# CC40_ROM_Cart.net
KiCad netlist of a schematic drawn in EAGLE
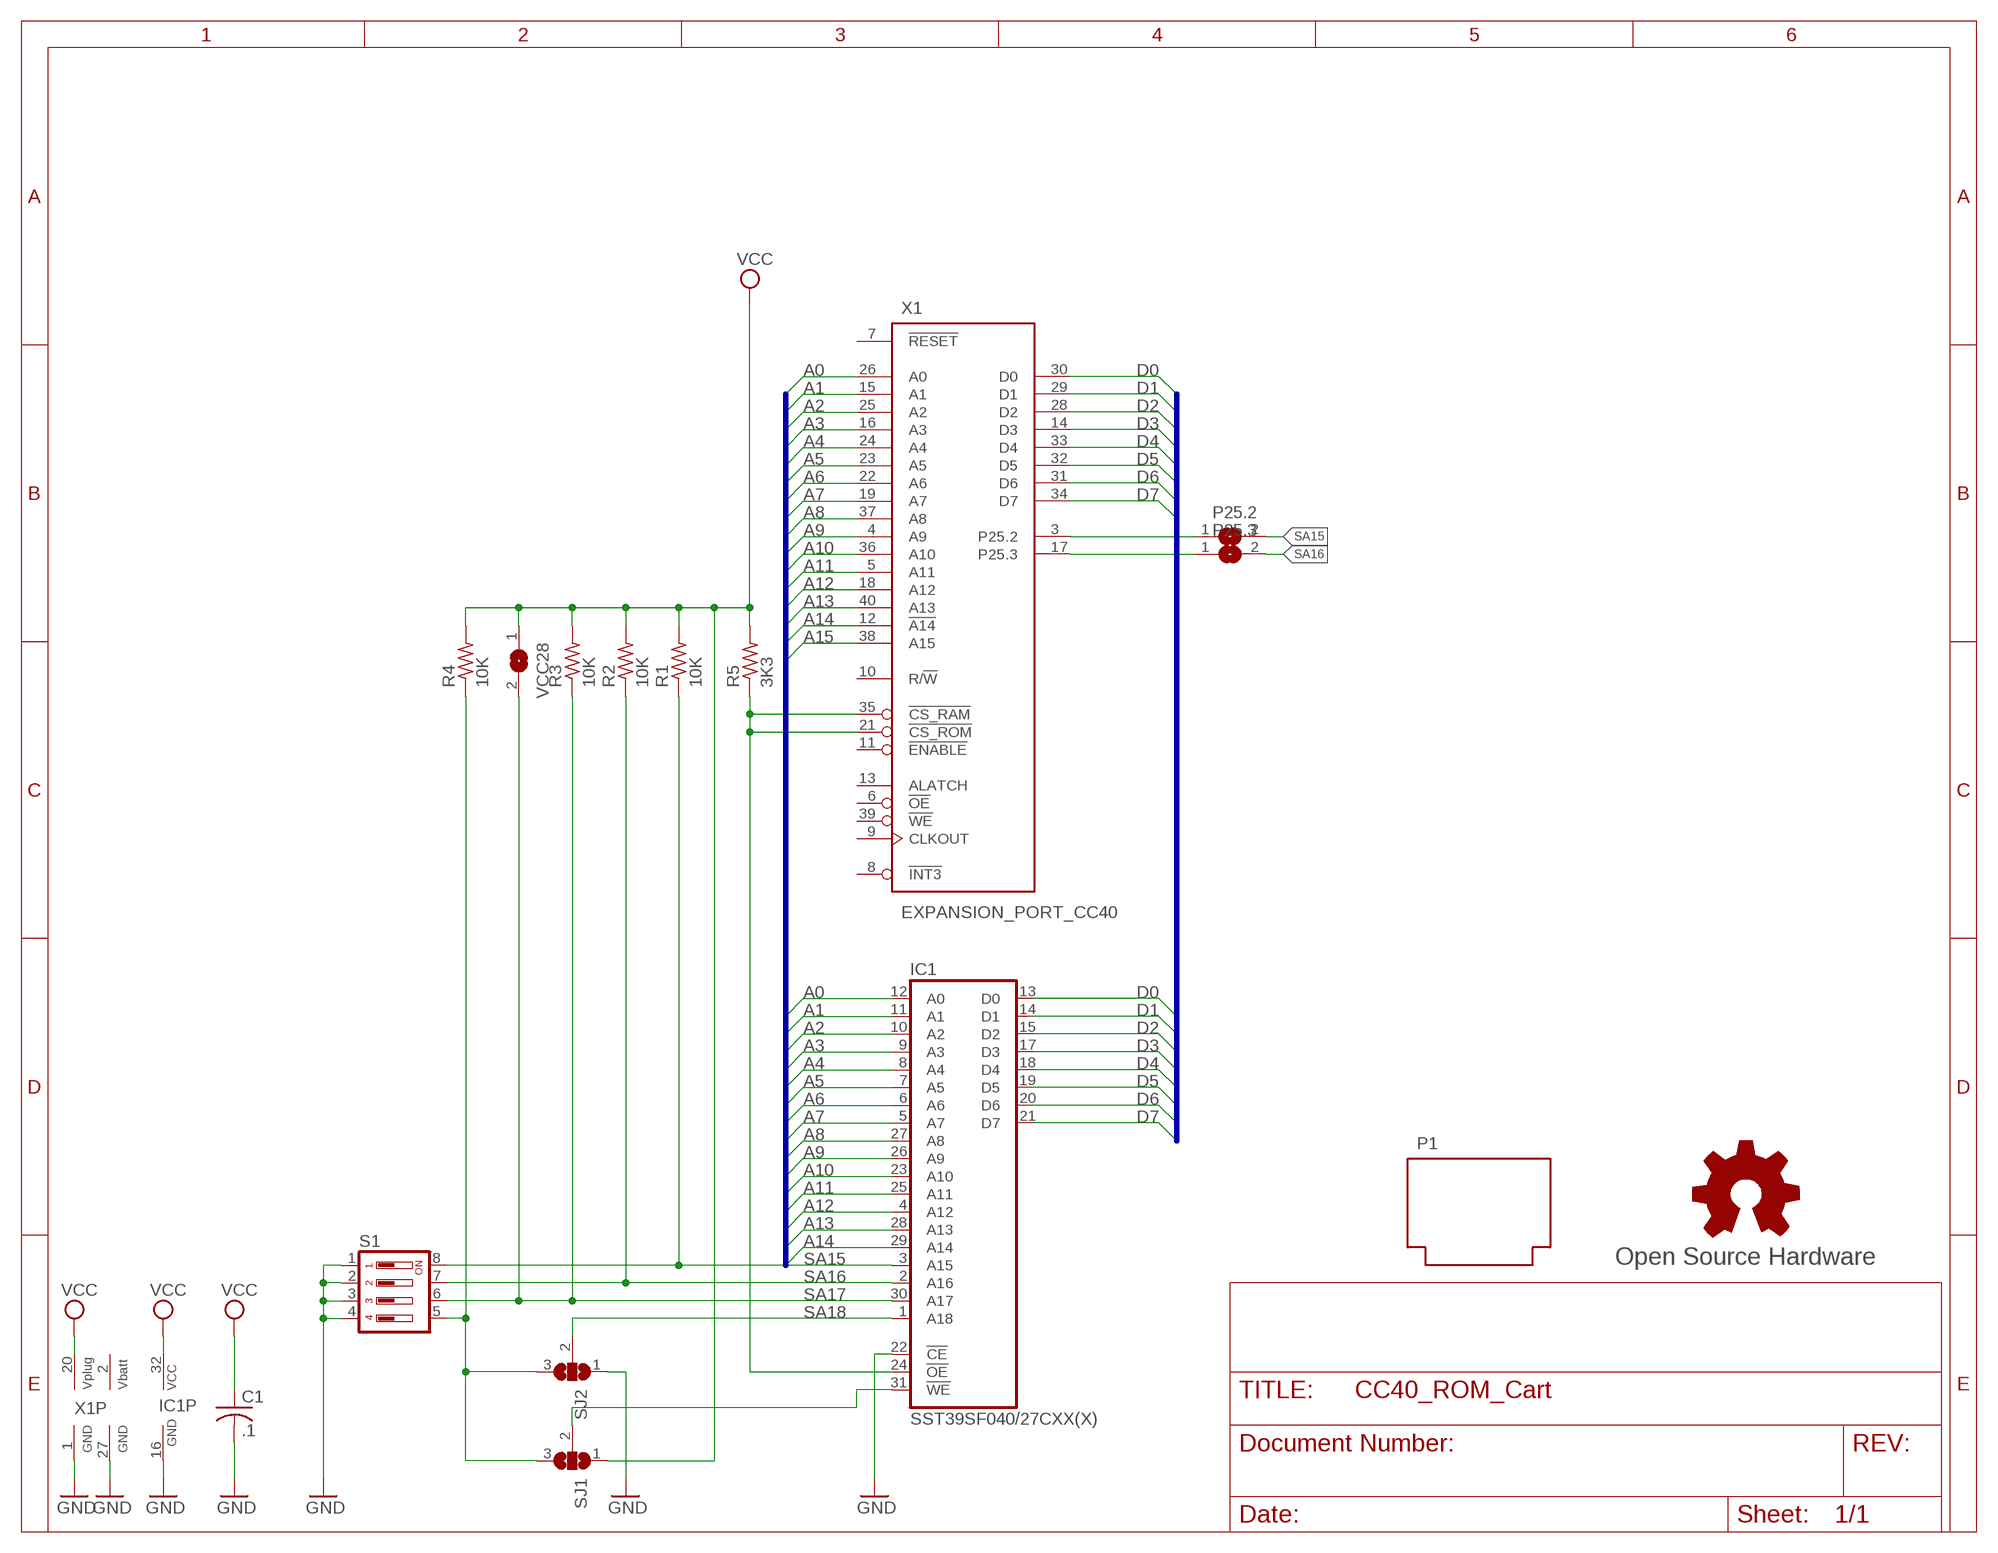
[diagram p0: schematic, sheet 1]

(export (version "E")
  (design (tool "Eeschema 10.0.6"))
  (components
    (comp (ref "C1")
      (value ".1")
      (footprint "eagle-import:C025-025X050")
      (libsource (lib "eagle-import") (part "C-US025-025X050"))
    )
    (comp (ref "GOLD_ORB_SM1")
      (value "Open Source Hardware")
      (footprint "eagle-import:OSHW_8MM")
      (libsource (lib "eagle-import") (part "OSHWLOGOLOGO8MM"))
    )
    (comp (ref "IC1")
      (value "SST39SF040/27CXX(X)")
      (footprint "eagle-import:DIL32-RP")
      (libsource (lib "eagle-import") (part "SST39SF040APHR"))
    )
    (comp (ref "P1")
      (value "CC40_CARTN")
      (footprint "eagle-import:CC40_CART_NOHOLE")
      (libsource (lib "eagle-import") (part "CC40_CARTN"))
    )
    (comp (ref "P25.2")
      (value "SJ")
      (footprint "eagle-import:SJ")
      (libsource (lib "eagle-import") (part "SJ"))
    )
    (comp (ref "P25.3")
      (value "SJ")
      (footprint "eagle-import:SJ")
      (libsource (lib "eagle-import") (part "SJ"))
    )
    (comp (ref "R1")
      (value "10K")
      (footprint "eagle-import:0204_7")
      (libsource (lib "eagle-import") (part "R-US_0204/7"))
    )
    (comp (ref "R2")
      (value "10K")
      (footprint "eagle-import:0204_7")
      (libsource (lib "eagle-import") (part "R-US_0204/7"))
    )
    (comp (ref "R3")
      (value "10K")
      (footprint "eagle-import:0204_7")
      (libsource (lib "eagle-import") (part "R-US_0204/7"))
    )
    (comp (ref "R4")
      (value "10K")
      (footprint "eagle-import:0204_7")
      (libsource (lib "eagle-import") (part "R-US_0204/7"))
    )
    (comp (ref "R5")
      (value "3K3")
      (footprint "eagle-import:0204_7")
      (libsource (lib "eagle-import") (part "R-US_0204/7"))
    )
    (comp (ref "S1")
      (value "DP04")
      (footprint "eagle-import:DP-04")
      (libsource (lib "eagle-import") (part "DP04"))
    )
    (comp (ref "SJ1")
      (value "SJ2W")
      (footprint "eagle-import:SJ_2")
      (libsource (lib "eagle-import") (part "SJ2W"))
    )
    (comp (ref "SJ2")
      (value "SJ2W")
      (footprint "eagle-import:SJ_2")
      (libsource (lib "eagle-import") (part "SJ2W"))
    )
    (comp (ref "VCC28")
      (value "SJ")
      (footprint "eagle-import:SJ")
      (libsource (lib "eagle-import") (part "SJ"))
    )
    (comp (ref "X1")
      (value "EXPANSION_PORT_CC40")
      (footprint "eagle-import:MA20-2(.050)")
      (libsource (lib "eagle-import") (part "EXPANSION_PORT_CC40"))
    )
  )
  (nets
    (net (code "1") (name "/A0") (class "Default")
      (node (ref "IC1") (pin "12") (pinfunction "A0_12") (pintype "input"))
      (node (ref "X1") (pin "26") (pinfunction "A0_26") (pintype "output"))
    )
    (net (code "2") (name "/A1") (class "Default")
      (node (ref "IC1") (pin "11") (pinfunction "A1_11") (pintype "input"))
      (node (ref "X1") (pin "15") (pinfunction "A1_15") (pintype "output"))
    )
    (net (code "3") (name "/A2") (class "Default")
      (node (ref "IC1") (pin "10") (pinfunction "A2_10") (pintype "input"))
      (node (ref "X1") (pin "25") (pinfunction "A2_25") (pintype "output"))
    )
    (net (code "4") (name "/A3") (class "Default")
      (node (ref "IC1") (pin "9") (pinfunction "A3_9") (pintype "input"))
      (node (ref "X1") (pin "16") (pinfunction "A3_16") (pintype "output"))
    )
    (net (code "5") (name "/A4") (class "Default")
      (node (ref "IC1") (pin "8") (pinfunction "A4_8") (pintype "input"))
      (node (ref "X1") (pin "24") (pinfunction "A4_24") (pintype "output"))
    )
    (net (code "6") (name "/A5") (class "Default")
      (node (ref "IC1") (pin "7") (pinfunction "A5_7") (pintype "input"))
      (node (ref "X1") (pin "23") (pinfunction "A5_23") (pintype "output"))
    )
    (net (code "7") (name "/A6") (class "Default")
      (node (ref "IC1") (pin "6") (pinfunction "A6_6") (pintype "input"))
      (node (ref "X1") (pin "22") (pinfunction "A6_22") (pintype "output"))
    )
    (net (code "8") (name "/A7") (class "Default")
      (node (ref "IC1") (pin "5") (pinfunction "A7_5") (pintype "input"))
      (node (ref "X1") (pin "19") (pinfunction "A7_19") (pintype "output"))
    )
    (net (code "9") (name "/A8") (class "Default")
      (node (ref "IC1") (pin "27") (pinfunction "A8_27") (pintype "input"))
      (node (ref "X1") (pin "37") (pinfunction "A8_37") (pintype "output"))
    )
    (net (code "10") (name "/A9") (class "Default")
      (node (ref "IC1") (pin "26") (pinfunction "A9_26") (pintype "input"))
      (node (ref "X1") (pin "4") (pinfunction "A9_4") (pintype "output"))
    )
    (net (code "11") (name "/A10") (class "Default")
      (node (ref "IC1") (pin "23") (pinfunction "A10_23") (pintype "input"))
      (node (ref "X1") (pin "36") (pinfunction "A10_36") (pintype "passive"))
    )
    (net (code "12") (name "/A11") (class "Default")
      (node (ref "IC1") (pin "25") (pinfunction "A11_25") (pintype "input"))
      (node (ref "X1") (pin "5") (pinfunction "A11_5") (pintype "output"))
    )
    (net (code "13") (name "/A12") (class "Default")
      (node (ref "IC1") (pin "4") (pinfunction "A12_4") (pintype "input"))
      (node (ref "X1") (pin "18") (pinfunction "A12_18") (pintype "output"))
    )
    (net (code "14") (name "/A13") (class "Default")
      (node (ref "IC1") (pin "28") (pinfunction "A13_28") (pintype "input"))
      (node (ref "X1") (pin "40") (pinfunction "A13_40") (pintype "output"))
    )
    (net (code "15") (name "/A14") (class "Default")
      (node (ref "IC1") (pin "29") (pinfunction "A14_29") (pintype "input"))
      (node (ref "X1") (pin "12") (pinfunction "~{A14}_12") (pintype "output"))
    )
    (net (code "16") (name "/A15") (class "Default")
      (node (ref "X1") (pin "38") (pinfunction "A15_38") (pintype "output"))
    )
    (net (code "17") (name "/D0") (class "Default")
      (node (ref "IC1") (pin "13") (pinfunction "D0_13") (pintype "bidirectional"))
      (node (ref "X1") (pin "30") (pinfunction "D0_30") (pintype "bidirectional"))
    )
    (net (code "18") (name "/D1") (class "Default")
      (node (ref "IC1") (pin "14") (pinfunction "D1_14") (pintype "bidirectional"))
      (node (ref "X1") (pin "29") (pinfunction "D1_29") (pintype "bidirectional"))
    )
    (net (code "19") (name "/D2") (class "Default")
      (node (ref "IC1") (pin "15") (pinfunction "D2_15") (pintype "bidirectional"))
      (node (ref "X1") (pin "28") (pinfunction "D2_28") (pintype "bidirectional"))
    )
    (net (code "20") (name "/D3") (class "Default")
      (node (ref "IC1") (pin "17") (pinfunction "D3_17") (pintype "bidirectional"))
      (node (ref "X1") (pin "14") (pinfunction "D3_14") (pintype "bidirectional"))
    )
    (net (code "21") (name "/D4") (class "Default")
      (node (ref "IC1") (pin "18") (pinfunction "D4_18") (pintype "bidirectional"))
      (node (ref "X1") (pin "33") (pinfunction "D4_33") (pintype "bidirectional"))
    )
    (net (code "22") (name "/D5") (class "Default")
      (node (ref "IC1") (pin "19") (pinfunction "D5_19") (pintype "bidirectional"))
      (node (ref "X1") (pin "32") (pinfunction "D5_32") (pintype "bidirectional"))
    )
    (net (code "23") (name "/D6") (class "Default")
      (node (ref "IC1") (pin "20") (pinfunction "D6_20") (pintype "bidirectional"))
      (node (ref "X1") (pin "31") (pinfunction "D6_31") (pintype "bidirectional"))
    )
    (net (code "24") (name "/D7") (class "Default")
      (node (ref "IC1") (pin "21") (pinfunction "D7_21") (pintype "bidirectional"))
      (node (ref "X1") (pin "34") (pinfunction "D7_34") (pintype "bidirectional"))
    )
    (net (code "25") (name "/SA17") (class "Default")
      (node (ref "IC1") (pin "30") (pinfunction "A17_30") (pintype "input"))
      (node (ref "R3") (pin "1") (pinfunction "1_1") (pintype "passive"))
      (node (ref "S1") (pin "6") (pinfunction "6_6") (pintype "passive"))
      (node (ref "VCC28") (pin "2") (pinfunction "2_2") (pintype "passive"))
    )
    (net (code "26") (name "/SA18") (class "Default")
      (node (ref "IC1") (pin "1") (pinfunction "A18_1") (pintype "input"))
      (node (ref "SJ2") (pin "2") (pinfunction "2_2") (pintype "passive"))
    )
    (net (code "27") (name "/VBATT") (class "Default")
      (node (ref "X1") (pin "2") (pinfunction "VBATT_2") (pintype "power_in"))
    )
    (net (code "28") (name "GND") (class "Default")
      (node (ref "C1") (pin "2") (pinfunction "2_2") (pintype "passive"))
      (node (ref "IC1") (pin "16") (pinfunction "GND_16") (pintype "power_in"))
      (node (ref "IC1") (pin "22") (pinfunction "~{CE}_22") (pintype "input"))
      (node (ref "S1") (pin "1") (pinfunction "1_1") (pintype "passive"))
      (node (ref "S1") (pin "2") (pinfunction "2_2") (pintype "passive"))
      (node (ref "S1") (pin "3") (pinfunction "3_3") (pintype "passive"))
      (node (ref "S1") (pin "4") (pinfunction "4_4") (pintype "passive"))
      (node (ref "SJ2") (pin "1") (pinfunction "1_1") (pintype "passive"))
      (node (ref "X1") (pin "1") (pinfunction "GND_1") (pintype "power_in"))
      (node (ref "X1") (pin "27") (pinfunction "GND_27") (pintype "power_in"))
    )
    (net (code "29") (name "Net-(IC1A-~{OE})") (class "Default")
      (node (ref "IC1") (pin "24") (pinfunction "~{OE}_24") (pintype "input"))
      (node (ref "R5") (pin "1") (pinfunction "1_1") (pintype "passive"))
      (node (ref "X1") (pin "21") (pinfunction "~{CS_ROM}_21") (pintype "output"))
      (node (ref "X1") (pin "35") (pinfunction "~{CS_RAM}_35") (pintype "output"))
    )
    (net (code "30") (name "Net-(IC1A-~{WE})") (class "Default")
      (node (ref "IC1") (pin "31") (pinfunction "~{WE}_31") (pintype "input"))
      (node (ref "SJ1") (pin "2") (pinfunction "2_2") (pintype "passive"))
    )
    (net (code "31") (name "Net-(R4-Pad1)") (class "Default")
      (node (ref "R4") (pin "1") (pinfunction "1_1") (pintype "passive"))
      (node (ref "S1") (pin "5") (pinfunction "5_5") (pintype "passive"))
      (node (ref "SJ1") (pin "3") (pinfunction "3_3") (pintype "passive"))
      (node (ref "SJ2") (pin "3") (pinfunction "3_3") (pintype "passive"))
    )
    (net (code "32") (name "Net-(X1B-P25.2)") (class "Default")
      (node (ref "P25.2") (pin "1") (pinfunction "1_1") (pintype "passive"))
      (node (ref "X1") (pin "3") (pinfunction "P25.2_3") (pintype "bidirectional"))
    )
    (net (code "33") (name "Net-(X1B-P25.3)") (class "Default")
      (node (ref "P25.3") (pin "1") (pinfunction "1_1") (pintype "passive"))
      (node (ref "X1") (pin "17") (pinfunction "P25.3_17") (pintype "bidirectional"))
    )
    (net (code "34") (name "SA15") (class "Default")
      (node (ref "IC1") (pin "3") (pinfunction "A15_3") (pintype "input"))
      (node (ref "P25.2") (pin "2") (pinfunction "2_2") (pintype "passive"))
      (node (ref "R1") (pin "1") (pinfunction "1_1") (pintype "passive"))
      (node (ref "S1") (pin "8") (pinfunction "8_8") (pintype "passive"))
    )
    (net (code "35") (name "SA16") (class "Default")
      (node (ref "IC1") (pin "2") (pinfunction "A16_2") (pintype "input"))
      (node (ref "P25.3") (pin "2") (pinfunction "2_2") (pintype "passive"))
      (node (ref "R2") (pin "1") (pinfunction "1_1") (pintype "passive"))
      (node (ref "S1") (pin "7") (pinfunction "7_7") (pintype "passive"))
    )
    (net (code "36") (name "VCC") (class "Default")
      (node (ref "C1") (pin "1") (pinfunction "1_1") (pintype "passive"))
      (node (ref "IC1") (pin "32") (pinfunction "VCC_32") (pintype "power_in"))
      (node (ref "R1") (pin "2") (pinfunction "2_2") (pintype "passive"))
      (node (ref "R2") (pin "2") (pinfunction "2_2") (pintype "passive"))
      (node (ref "R3") (pin "2") (pinfunction "2_2") (pintype "passive"))
      (node (ref "R4") (pin "2") (pinfunction "2_2") (pintype "passive"))
      (node (ref "R5") (pin "2") (pinfunction "2_2") (pintype "passive"))
      (node (ref "SJ1") (pin "1") (pinfunction "1_1") (pintype "passive"))
      (node (ref "VCC28") (pin "1") (pinfunction "1_1") (pintype "passive"))
      (node (ref "X1") (pin "20") (pinfunction "VPLUG_20") (pintype "power_in"))
    )
    (net (code "37") (name "unconnected-(X1B-ALATCH-Pad13)") (class "Default")
      (node (ref "X1") (pin "13") (pinfunction "ALATCH_13") (pintype "output"))
    )
    (net (code "38") (name "unconnected-(X1B-CLKOUT-Pad9)") (class "Default")
      (node (ref "X1") (pin "9") (pinfunction "CLKOUT_9") (pintype "output"))
    )
    (net (code "39") (name "unconnected-(X1B-R{slash}~{W}-Pad10)") (class "Default")
      (node (ref "X1") (pin "10") (pinfunction "R/~{W}_10") (pintype "output"))
    )
    (net (code "40") (name "unconnected-(X1B-~{ENABLE}-Pad11)") (class "Default")
      (node (ref "X1") (pin "11") (pinfunction "~{ENABLE}_11") (pintype "output"))
    )
    (net (code "41") (name "unconnected-(X1B-~{INT3}-Pad8)") (class "Default")
      (node (ref "X1") (pin "8") (pinfunction "~{INT3}_8") (pintype "open_collector"))
    )
    (net (code "42") (name "unconnected-(X1B-~{OE}-Pad6)") (class "Default")
      (node (ref "X1") (pin "6") (pinfunction "~{OE}_6") (pintype "output"))
    )
    (net (code "43") (name "unconnected-(X1B-~{RESET}-Pad7)") (class "Default")
      (node (ref "X1") (pin "7") (pinfunction "~{RESET}_7") (pintype "open_collector"))
    )
    (net (code "44") (name "unconnected-(X1B-~{WE}-Pad39)") (class "Default")
      (node (ref "X1") (pin "39") (pinfunction "~{WE}_39") (pintype "output"))
    )
  )
)
